# pri_shield_leds.net
KiCad netlist of a schematic drawn in EAGLE
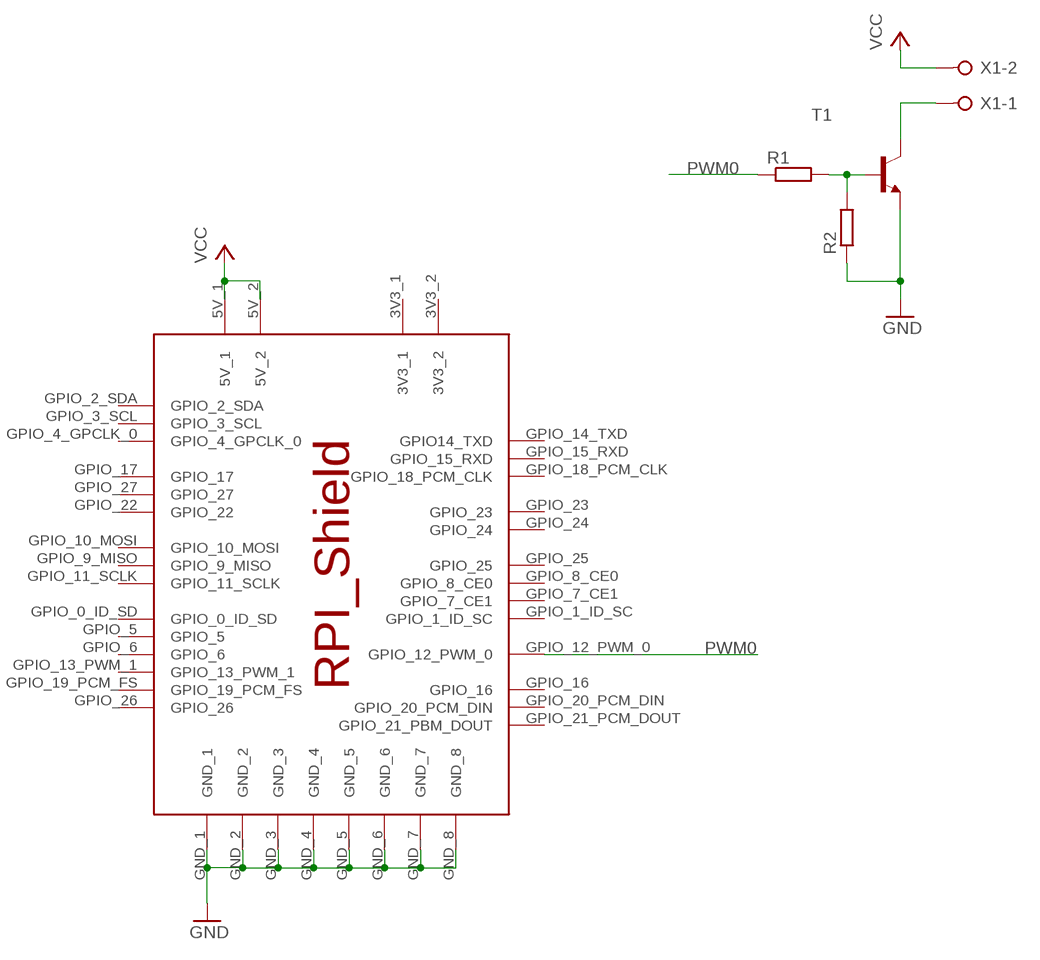
[diagram p0: schematic, sheet 1]

(export (version "E")
  (design (tool "Eeschema 10.0.6"))
  (components
    (comp (ref "R1")
      (value "R-EU_R1206")
      (footprint "eagle-import:R1206")
      (libsource (lib "eagle-import") (part "R-EU_R1206"))
    )
    (comp (ref "R2")
      (value "R-EU_R1206")
      (footprint "eagle-import:R1206")
      (libsource (lib "eagle-import") (part "R-EU_R1206"))
    )
    (comp (ref "T1")
      (value "-NPN-SOT223")
      (footprint "eagle-import:SOT223")
      (libsource (lib "eagle-import") (part "-NPN-SOT223"))
    )
    (comp (ref "U$1")
      (value "RPI_SHIELD")
      (footprint "eagle-import:RPI_SHIELD")
      (libsource (lib "eagle-import") (part "RPI_SHIELD"))
    )
    (comp (ref "X1")
      (value "W237-02P")
      (footprint "eagle-import:W237-132")
      (libsource (lib "eagle-import") (part "W237-02P"))
    )
  )
  (nets
    (net (code "1") (name "/PWM0") (class "Default")
      (node (ref "R1") (pin "1") (pinfunction "1_1") (pintype "passive"))
      (node (ref "U$1") (pin "GPIO_12_PWM_0") (pinfunction "GPIO_12_PWM_0_GPIO_12_PWM_0") (pintype "bidirectional"))
    )
    (net (code "2") (name "GND") (class "Default")
      (node (ref "R2") (pin "1") (pinfunction "1_1") (pintype "passive"))
      (node (ref "T1") (pin "3") (pinfunction "E_3") (pintype "passive"))
      (node (ref "U$1") (pin "GND_1") (pinfunction "GND_1_GND_1") (pintype "bidirectional"))
      (node (ref "U$1") (pin "GND_2") (pinfunction "GND_2_GND_2") (pintype "bidirectional"))
      (node (ref "U$1") (pin "GND_3") (pinfunction "GND_3_GND_3") (pintype "bidirectional"))
      (node (ref "U$1") (pin "GND_4") (pinfunction "GND_4_GND_4") (pintype "bidirectional"))
      (node (ref "U$1") (pin "GND_5") (pinfunction "GND_5_GND_5") (pintype "bidirectional"))
      (node (ref "U$1") (pin "GND_6") (pinfunction "GND_6_GND_6") (pintype "bidirectional"))
      (node (ref "U$1") (pin "GND_7") (pinfunction "GND_7_GND_7") (pintype "bidirectional"))
      (node (ref "U$1") (pin "GND_8") (pinfunction "GND_8_GND_8") (pintype "bidirectional"))
    )
    (net (code "3") (name "Net-(T1-B)") (class "Default")
      (node (ref "R1") (pin "2") (pinfunction "2_2") (pintype "passive"))
      (node (ref "R2") (pin "2") (pinfunction "2_2") (pintype "passive"))
      (node (ref "T1") (pin "1") (pinfunction "B_1") (pintype "passive"))
    )
    (net (code "4") (name "Net-(T1-C)") (class "Default")
      (node (ref "T1") (pin "4") (pinfunction "C_4") (pintype "passive"))
      (node (ref "X1") (pin "1") (pinfunction "KL_1") (pintype "passive"))
    )
    (net (code "5") (name "VCC") (class "Default")
      (node (ref "U$1") (pin "5V_1") (pinfunction "5V_1_5V_1") (pintype "bidirectional"))
      (node (ref "U$1") (pin "5V_2") (pinfunction "5V_2_5V_2") (pintype "bidirectional"))
      (node (ref "X1") (pin "2") (pinfunction "KL_2") (pintype "passive"))
    )
    (net (code "6") (name "unconnected-(U$1-GPIO14_TXD-PadGPIO_14_TXD)") (class "Default")
      (node (ref "U$1") (pin "GPIO_14_TXD") (pinfunction "GPIO14_TXD_GPIO_14_TXD") (pintype "bidirectional"))
    )
    (net (code "7") (name "unconnected-(U$1-GPIO_21_PBM_DOUT-PadGPIO_21_PCM_DOUT)") (class "Default")
      (node (ref "U$1") (pin "GPIO_21_PCM_DOUT") (pinfunction "GPIO_21_PBM_DOUT_GPIO_21_PCM_DOUT") (pintype "bidirectional"))
    )
    (net (code "8") (name "unconnected-(U$1-Pad3V3_1)") (class "Default")
      (node (ref "U$1") (pin "3V3_1") (pinfunction "3V3_1_3V3_1") (pintype "bidirectional"))
    )
    (net (code "9") (name "unconnected-(U$1-Pad3V3_2)") (class "Default")
      (node (ref "U$1") (pin "3V3_2") (pinfunction "3V3_2_3V3_2") (pintype "bidirectional"))
    )
    (net (code "10") (name "unconnected-(U$1-PadGPIO_0_ID_SD)") (class "Default")
      (node (ref "U$1") (pin "GPIO_0_ID_SD") (pinfunction "GPIO_0_ID_SD_GPIO_0_ID_SD") (pintype "bidirectional"))
    )
    (net (code "11") (name "unconnected-(U$1-PadGPIO_1_ID_SC)") (class "Default")
      (node (ref "U$1") (pin "GPIO_1_ID_SC") (pinfunction "GPIO_1_ID_SC_GPIO_1_ID_SC") (pintype "bidirectional"))
    )
    (net (code "12") (name "unconnected-(U$1-PadGPIO_2_SDA)") (class "Default")
      (node (ref "U$1") (pin "GPIO_2_SDA") (pinfunction "GPIO_2_SDA_GPIO_2_SDA") (pintype "bidirectional"))
    )
    (net (code "13") (name "unconnected-(U$1-PadGPIO_3_SCL)") (class "Default")
      (node (ref "U$1") (pin "GPIO_3_SCL") (pinfunction "GPIO_3_SCL_GPIO_3_SCL") (pintype "bidirectional"))
    )
    (net (code "14") (name "unconnected-(U$1-PadGPIO_4_GPCLK_0)") (class "Default")
      (node (ref "U$1") (pin "GPIO_4_GPCLK_0") (pinfunction "GPIO_4_GPCLK_0_GPIO_4_GPCLK_0") (pintype "bidirectional"))
    )
    (net (code "15") (name "unconnected-(U$1-PadGPIO_5)") (class "Default")
      (node (ref "U$1") (pin "GPIO_5") (pinfunction "GPIO_5_GPIO_5") (pintype "bidirectional"))
    )
    (net (code "16") (name "unconnected-(U$1-PadGPIO_6)") (class "Default")
      (node (ref "U$1") (pin "GPIO_6") (pinfunction "GPIO_6_GPIO_6") (pintype "bidirectional"))
    )
    (net (code "17") (name "unconnected-(U$1-PadGPIO_7_CE1)") (class "Default")
      (node (ref "U$1") (pin "GPIO_7_CE1") (pinfunction "GPIO_7_CE1_GPIO_7_CE1") (pintype "bidirectional"))
    )
    (net (code "18") (name "unconnected-(U$1-PadGPIO_8_CE0)") (class "Default")
      (node (ref "U$1") (pin "GPIO_8_CE0") (pinfunction "GPIO_8_CE0_GPIO_8_CE0") (pintype "bidirectional"))
    )
    (net (code "19") (name "unconnected-(U$1-PadGPIO_9_MISO)") (class "Default")
      (node (ref "U$1") (pin "GPIO_9_MISO") (pinfunction "GPIO_9_MISO_GPIO_9_MISO") (pintype "bidirectional"))
    )
    (net (code "20") (name "unconnected-(U$1-PadGPIO_10_MOSI)") (class "Default")
      (node (ref "U$1") (pin "GPIO_10_MOSI") (pinfunction "GPIO_10_MOSI_GPIO_10_MOSI") (pintype "bidirectional"))
    )
    (net (code "21") (name "unconnected-(U$1-PadGPIO_11_SCLK)") (class "Default")
      (node (ref "U$1") (pin "GPIO_11_SCLK") (pinfunction "GPIO_11_SCLK_GPIO_11_SCLK") (pintype "bidirectional"))
    )
    (net (code "22") (name "unconnected-(U$1-PadGPIO_13_PWM_1)") (class "Default")
      (node (ref "U$1") (pin "GPIO_13_PWM_1") (pinfunction "GPIO_13_PWM_1_GPIO_13_PWM_1") (pintype "bidirectional"))
    )
    (net (code "23") (name "unconnected-(U$1-PadGPIO_15_RXD)") (class "Default")
      (node (ref "U$1") (pin "GPIO_15_RXD") (pinfunction "GPIO_15_RXD_GPIO_15_RXD") (pintype "bidirectional"))
    )
    (net (code "24") (name "unconnected-(U$1-PadGPIO_16)") (class "Default")
      (node (ref "U$1") (pin "GPIO_16") (pinfunction "GPIO_16_GPIO_16") (pintype "bidirectional"))
    )
    (net (code "25") (name "unconnected-(U$1-PadGPIO_17)") (class "Default")
      (node (ref "U$1") (pin "GPIO_17") (pinfunction "GPIO_17_GPIO_17") (pintype "bidirectional"))
    )
    (net (code "26") (name "unconnected-(U$1-PadGPIO_18_PCM_CLK)") (class "Default")
      (node (ref "U$1") (pin "GPIO_18_PCM_CLK") (pinfunction "GPIO_18_PCM_CLK_GPIO_18_PCM_CLK") (pintype "bidirectional"))
    )
    (net (code "27") (name "unconnected-(U$1-PadGPIO_19_PCM_FS)") (class "Default")
      (node (ref "U$1") (pin "GPIO_19_PCM_FS") (pinfunction "GPIO_19_PCM_FS_GPIO_19_PCM_FS") (pintype "bidirectional"))
    )
    (net (code "28") (name "unconnected-(U$1-PadGPIO_20_PCM_DIN)") (class "Default")
      (node (ref "U$1") (pin "GPIO_20_PCM_DIN") (pinfunction "GPIO_20_PCM_DIN_GPIO_20_PCM_DIN") (pintype "bidirectional"))
    )
    (net (code "29") (name "unconnected-(U$1-PadGPIO_22)") (class "Default")
      (node (ref "U$1") (pin "GPIO_22") (pinfunction "GPIO_22_GPIO_22") (pintype "bidirectional"))
    )
    (net (code "30") (name "unconnected-(U$1-PadGPIO_23)") (class "Default")
      (node (ref "U$1") (pin "GPIO_23") (pinfunction "GPIO_23_GPIO_23") (pintype "bidirectional"))
    )
    (net (code "31") (name "unconnected-(U$1-PadGPIO_24)") (class "Default")
      (node (ref "U$1") (pin "GPIO_24") (pinfunction "GPIO_24_GPIO_24") (pintype "bidirectional"))
    )
    (net (code "32") (name "unconnected-(U$1-PadGPIO_25)") (class "Default")
      (node (ref "U$1") (pin "GPIO_25") (pinfunction "GPIO_25_GPIO_25") (pintype "bidirectional"))
    )
    (net (code "33") (name "unconnected-(U$1-PadGPIO_26)") (class "Default")
      (node (ref "U$1") (pin "GPIO_26") (pinfunction "GPIO_26_GPIO_26") (pintype "bidirectional"))
    )
    (net (code "34") (name "unconnected-(U$1-PadGPIO_27)") (class "Default")
      (node (ref "U$1") (pin "GPIO_27") (pinfunction "GPIO_27_GPIO_27") (pintype "bidirectional"))
    )
  )
)
